# schematich.net
KiCad netlist of a schematic drawn in EAGLE
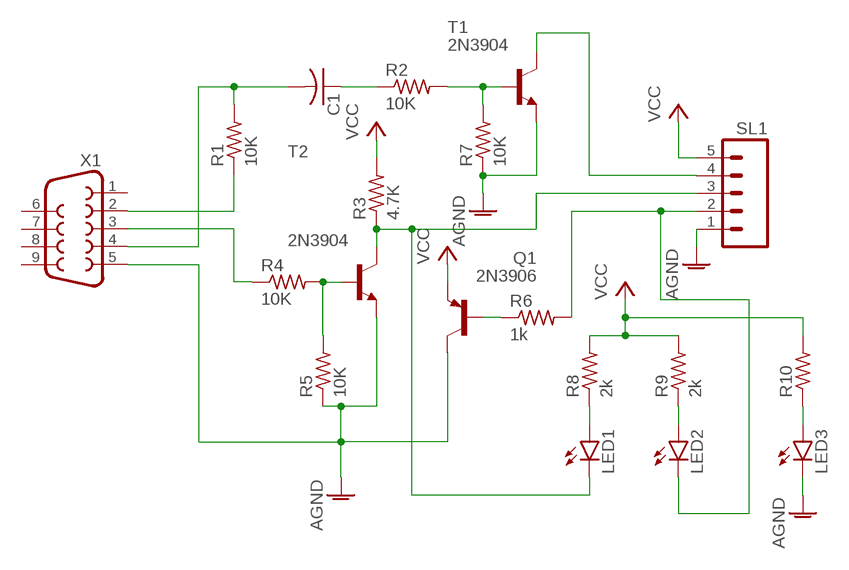
[diagram p0: schematic, sheet 1]

(export (version "E")
  (design (tool "Eeschema 10.0.6"))
  (components
    (comp (ref "C1")
      (value "C-USC0805")
      (footprint "eagle-import:C0805")
      (libsource (lib "eagle-import") (part "C-USC0805"))
    )
    (comp (ref "LED1")
      (value "LED3MM")
      (footprint "eagle-import:LED3MM")
      (libsource (lib "eagle-import") (part "LED3MM"))
    )
    (comp (ref "LED2")
      (value "LED3MM")
      (footprint "eagle-import:LED3MM")
      (libsource (lib "eagle-import") (part "LED3MM"))
    )
    (comp (ref "LED3")
      (value "LED3MM")
      (footprint "eagle-import:LED3MM")
      (libsource (lib "eagle-import") (part "LED3MM"))
    )
    (comp (ref "Q1")
      (value "2N3906")
      (footprint "eagle-import:TO92")
      (libsource (lib "eagle-import") (part "2N3906"))
    )
    (comp (ref "R1")
      (value "10K")
      (footprint "eagle-import:M1406")
      (libsource (lib "eagle-import") (part "R-US_M1406"))
    )
    (comp (ref "R2")
      (value "10K")
      (footprint "eagle-import:M1406")
      (libsource (lib "eagle-import") (part "R-US_M1406"))
    )
    (comp (ref "R3")
      (value "4.7K")
      (footprint "eagle-import:M1406")
      (libsource (lib "eagle-import") (part "R-US_M1406"))
    )
    (comp (ref "R4")
      (value "10K")
      (footprint "eagle-import:M1406")
      (libsource (lib "eagle-import") (part "R-US_M1406"))
    )
    (comp (ref "R5")
      (value "10K")
      (footprint "eagle-import:M1406")
      (libsource (lib "eagle-import") (part "R-US_M1406"))
    )
    (comp (ref "R6")
      (value "1k")
      (footprint "eagle-import:M1406")
      (libsource (lib "eagle-import") (part "R-US_M1406"))
    )
    (comp (ref "R7")
      (value "10K")
      (footprint "eagle-import:M1406")
      (libsource (lib "eagle-import") (part "R-US_M1406"))
    )
    (comp (ref "R8")
      (value "2k")
      (footprint "eagle-import:M0805")
      (libsource (lib "eagle-import") (part "R-US_M0805"))
    )
    (comp (ref "R9")
      (value "2k")
      (footprint "eagle-import:M0805")
      (libsource (lib "eagle-import") (part "R-US_M0805"))
    )
    (comp (ref "R10")
      (value "R-US_M0805")
      (footprint "eagle-import:M0805")
      (libsource (lib "eagle-import") (part "R-US_M0805"))
    )
    (comp (ref "SL1")
      (value "M05")
      (footprint "eagle-import:05P")
      (libsource (lib "eagle-import") (part "M05"))
    )
    (comp (ref "T1")
      (value "2N3904")
      (footprint "eagle-import:TO92")
      (libsource (lib "eagle-import") (part "2N3904"))
    )
    (comp (ref "T2")
      (value "2N3904")
      (footprint "eagle-import:TO92")
      (libsource (lib "eagle-import") (part "2N3904"))
    )
    (comp (ref "X1")
      (value "F09HP")
      (footprint "eagle-import:F09HP")
      (libsource (lib "eagle-import") (part "F09HP"))
    )
  )
  (nets
    (net (code "1") (name "AGND") (class "Default")
      (node (ref "LED3") (pin "K") (pinfunction "C_K") (pintype "passive"))
      (node (ref "Q1") (pin "1") (pinfunction "C_1") (pintype "passive"))
      (node (ref "R5") (pin "1") (pinfunction "1_1") (pintype "passive"))
      (node (ref "R7") (pin "1") (pinfunction "1_1") (pintype "passive"))
      (node (ref "SL1") (pin "1") (pinfunction "1_1") (pintype "passive"))
      (node (ref "T1") (pin "3") (pinfunction "E_3") (pintype "passive"))
      (node (ref "T2") (pin "3") (pinfunction "E_3") (pintype "passive"))
      (node (ref "X1") (pin "5") (pinfunction "5_5") (pintype "passive"))
    )
    (net (code "2") (name "Net-(C1-Pad1)") (class "Default")
      (node (ref "C1") (pin "1") (pinfunction "1_1") (pintype "passive"))
      (node (ref "R2") (pin "1") (pinfunction "1_1") (pintype "passive"))
    )
    (net (code "3") (name "Net-(C1-Pad2)") (class "Default")
      (node (ref "C1") (pin "2") (pinfunction "2_2") (pintype "passive"))
      (node (ref "R1") (pin "2") (pinfunction "2_2") (pintype "passive"))
      (node (ref "X1") (pin "4") (pinfunction "4_4") (pintype "passive"))
    )
    (net (code "4") (name "Net-(LED1-C)") (class "Default")
      (node (ref "LED1") (pin "K") (pinfunction "C_K") (pintype "passive"))
      (node (ref "R3") (pin "1") (pinfunction "1_1") (pintype "passive"))
      (node (ref "SL1") (pin "3") (pinfunction "3_3") (pintype "passive"))
      (node (ref "T2") (pin "1") (pinfunction "C_1") (pintype "passive"))
    )
    (net (code "5") (name "Net-(LED1-PadA)") (class "Default")
      (node (ref "LED1") (pin "A") (pinfunction "A_A") (pintype "passive"))
      (node (ref "R8") (pin "1") (pinfunction "1_1") (pintype "passive"))
    )
    (net (code "6") (name "Net-(LED2-C)") (class "Default")
      (node (ref "LED2") (pin "K") (pinfunction "C_K") (pintype "passive"))
      (node (ref "R6") (pin "2") (pinfunction "2_2") (pintype "passive"))
      (node (ref "SL1") (pin "2") (pinfunction "2_2") (pintype "passive"))
    )
    (net (code "7") (name "Net-(LED2-PadA)") (class "Default")
      (node (ref "LED2") (pin "A") (pinfunction "A_A") (pintype "passive"))
      (node (ref "R9") (pin "1") (pinfunction "1_1") (pintype "passive"))
    )
    (net (code "8") (name "Net-(LED3-PadA)") (class "Default")
      (node (ref "LED3") (pin "A") (pinfunction "A_A") (pintype "passive"))
      (node (ref "R10") (pin "1") (pinfunction "1_1") (pintype "passive"))
    )
    (net (code "9") (name "Net-(Q1-B)") (class "Default")
      (node (ref "Q1") (pin "2") (pinfunction "B_2") (pintype "passive"))
      (node (ref "R6") (pin "1") (pinfunction "1_1") (pintype "passive"))
    )
    (net (code "10") (name "Net-(R1-Pad1)") (class "Default")
      (node (ref "R1") (pin "1") (pinfunction "1_1") (pintype "passive"))
      (node (ref "X1") (pin "2") (pinfunction "2_2") (pintype "passive"))
    )
    (net (code "11") (name "Net-(R4-Pad1)") (class "Default")
      (node (ref "R4") (pin "1") (pinfunction "1_1") (pintype "passive"))
      (node (ref "X1") (pin "3") (pinfunction "3_3") (pintype "passive"))
    )
    (net (code "12") (name "Net-(T1-B)") (class "Default")
      (node (ref "R2") (pin "2") (pinfunction "2_2") (pintype "passive"))
      (node (ref "R7") (pin "2") (pinfunction "2_2") (pintype "passive"))
      (node (ref "T1") (pin "2") (pinfunction "B_2") (pintype "passive"))
    )
    (net (code "13") (name "Net-(T1-C)") (class "Default")
      (node (ref "SL1") (pin "4") (pinfunction "4_4") (pintype "passive"))
      (node (ref "T1") (pin "1") (pinfunction "C_1") (pintype "passive"))
    )
    (net (code "14") (name "Net-(T2-B)") (class "Default")
      (node (ref "R4") (pin "2") (pinfunction "2_2") (pintype "passive"))
      (node (ref "R5") (pin "2") (pinfunction "2_2") (pintype "passive"))
      (node (ref "T2") (pin "2") (pinfunction "B_2") (pintype "passive"))
    )
    (net (code "15") (name "VCC") (class "Default")
      (node (ref "Q1") (pin "3") (pinfunction "E_3") (pintype "passive"))
      (node (ref "R10") (pin "2") (pinfunction "2_2") (pintype "passive"))
      (node (ref "R3") (pin "2") (pinfunction "2_2") (pintype "passive"))
      (node (ref "R8") (pin "2") (pinfunction "2_2") (pintype "passive"))
      (node (ref "R9") (pin "2") (pinfunction "2_2") (pintype "passive"))
      (node (ref "SL1") (pin "5") (pinfunction "5_5") (pintype "passive"))
    )
    (net (code "16") (name "unconnected-(X1-Pad1)") (class "Default")
      (node (ref "X1") (pin "1") (pinfunction "1_1") (pintype "passive"))
    )
    (net (code "17") (name "unconnected-(X1-Pad6)") (class "Default")
      (node (ref "X1") (pin "6") (pinfunction "6_6") (pintype "passive"))
    )
    (net (code "18") (name "unconnected-(X1-Pad7)") (class "Default")
      (node (ref "X1") (pin "7") (pinfunction "7_7") (pintype "passive"))
    )
    (net (code "19") (name "unconnected-(X1-Pad8)") (class "Default")
      (node (ref "X1") (pin "8") (pinfunction "8_8") (pintype "passive"))
    )
    (net (code "20") (name "unconnected-(X1-Pad9)") (class "Default")
      (node (ref "X1") (pin "9") (pinfunction "9_9") (pintype "passive"))
    )
  )
)
